# buttons_and_leds.net
KiCad netlist of a schematic drawn in Altium Designer
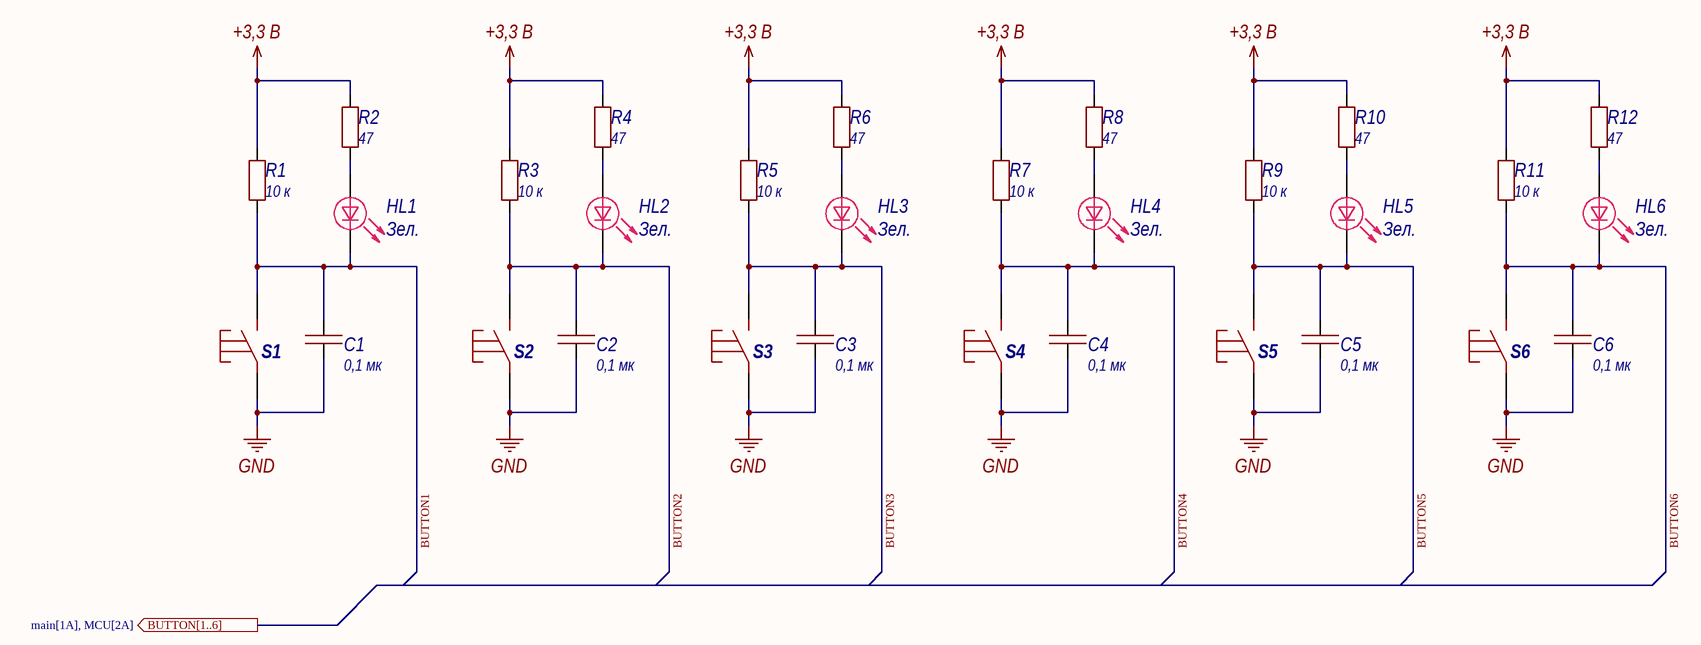
[diagram p0: buttons_and_leds.SchDoc]

(export (version "E")
  (design (tool "Eeschema 10.0.6"))
  (components
    (comp (ref "C1")
      (value "0,1 мк")
      (footprint "0603C")
      (description "Конденсатор 0603C ёмкостью 0,1 мк 10%, 50 В, X7R")
      (fields (field (name "PART NUMBER") "Capacitor_0,1u_10_50V_X7R_0603C") (field (name "TOLERANCE") "10%"))
      (libsource (lib "Hydrolib") (part "Capacitor"))
    )
    (comp (ref "C2")
      (value "0,1 мк")
      (footprint "0603C")
      (description "Конденсатор 0603C ёмкостью 0,1 мк 10%, 50 В, X7R")
      (fields (field (name "PART NUMBER") "Capacitor_0,1u_10_50V_X7R_0603C") (field (name "TOLERANCE") "10%"))
      (libsource (lib "Hydrolib") (part "Capacitor"))
    )
    (comp (ref "C3")
      (value "0,1 мк")
      (footprint "0603C")
      (description "Конденсатор 0603C ёмкостью 0,1 мк 10%, 50 В, X7R")
      (fields (field (name "PART NUMBER") "Capacitor_0,1u_10_50V_X7R_0603C") (field (name "TOLERANCE") "10%"))
      (libsource (lib "Hydrolib") (part "Capacitor"))
    )
    (comp (ref "C4")
      (value "0,1 мк")
      (footprint "0603C")
      (description "Конденсатор 0603C ёмкостью 0,1 мк 10%, 50 В, X7R")
      (fields (field (name "PART NUMBER") "Capacitor_0,1u_10_50V_X7R_0603C") (field (name "TOLERANCE") "10%"))
      (libsource (lib "Hydrolib") (part "Capacitor"))
    )
    (comp (ref "C5")
      (value "0,1 мк")
      (footprint "0603C")
      (description "Конденсатор 0603C ёмкостью 0,1 мк 10%, 50 В, X7R")
      (fields (field (name "PART NUMBER") "Capacitor_0,1u_10_50V_X7R_0603C") (field (name "TOLERANCE") "10%"))
      (libsource (lib "Hydrolib") (part "Capacitor"))
    )
    (comp (ref "C6")
      (value "0,1 мк")
      (footprint "0603C")
      (description "Конденсатор 0603C ёмкостью 0,1 мк 10%, 50 В, X7R")
      (fields (field (name "PART NUMBER") "Capacitor_0,1u_10_50V_X7R_0603C") (field (name "TOLERANCE") "10%"))
      (libsource (lib "Hydrolib") (part "Capacitor"))
    )
    (comp (ref "HL1")
      (value "LED")
      (footprint "0805D")
      (description "Светодиод")
      (fields (field (name "COLOR") "Зел."))
      (libsource (lib "Hydrolib") (part "LED"))
    )
    (comp (ref "HL2")
      (value "LED")
      (footprint "0805D")
      (description "Светодиод")
      (fields (field (name "COLOR") "Зел."))
      (libsource (lib "Hydrolib") (part "LED"))
    )
    (comp (ref "HL3")
      (value "LED")
      (footprint "0805D")
      (description "Светодиод")
      (fields (field (name "COLOR") "Зел."))
      (libsource (lib "Hydrolib") (part "LED"))
    )
    (comp (ref "HL4")
      (value "LED")
      (footprint "0805D")
      (description "Светодиод")
      (fields (field (name "COLOR") "Зел."))
      (libsource (lib "Hydrolib") (part "LED"))
    )
    (comp (ref "HL5")
      (value "LED")
      (footprint "0805D")
      (description "Светодиод")
      (fields (field (name "COLOR") "Зел."))
      (libsource (lib "Hydrolib") (part "LED"))
    )
    (comp (ref "HL6")
      (value "LED")
      (footprint "0805D")
      (description "Светодиод")
      (fields (field (name "COLOR") "Зел."))
      (libsource (lib "Hydrolib") (part "LED"))
    )
    (comp (ref "R1")
      (value "10 к")
      (footprint "0603R")
      (description "Резистор номиналом 10 кОм 1%")
      (fields (field (name "PART NUMBER") "Resistor_10k_1_0603") (field (name "TOLERANCE") "1%"))
      (libsource (lib "Hydrolib") (part "Resistor"))
    )
    (comp (ref "R2")
      (value "47")
      (footprint "0603R")
      (description "Резистор номиналом 47 Ом 1%")
      (fields (field (name "PART NUMBER") "Resistor_47_1_0603") (field (name "TOLERANCE") "1%"))
      (libsource (lib "Hydrolib") (part "Resistor"))
    )
    (comp (ref "R3")
      (value "10 к")
      (footprint "0603R")
      (description "Резистор номиналом 10 кОм 1%")
      (fields (field (name "PART NUMBER") "Resistor_10k_1_0603") (field (name "TOLERANCE") "1%"))
      (libsource (lib "Hydrolib") (part "Resistor"))
    )
    (comp (ref "R4")
      (value "47")
      (footprint "0603R")
      (description "Резистор номиналом 47 Ом 1%")
      (fields (field (name "PART NUMBER") "Resistor_47_1_0603") (field (name "TOLERANCE") "1%"))
      (libsource (lib "Hydrolib") (part "Resistor"))
    )
    (comp (ref "R5")
      (value "10 к")
      (footprint "0603R")
      (description "Резистор номиналом 10 кОм 1%")
      (fields (field (name "PART NUMBER") "Resistor_10k_1_0603") (field (name "TOLERANCE") "1%"))
      (libsource (lib "Hydrolib") (part "Resistor"))
    )
    (comp (ref "R6")
      (value "47")
      (footprint "0603R")
      (description "Резистор номиналом 47 Ом 1%")
      (fields (field (name "PART NUMBER") "Resistor_47_1_0603") (field (name "TOLERANCE") "1%"))
      (libsource (lib "Hydrolib") (part "Resistor"))
    )
    (comp (ref "R7")
      (value "10 к")
      (footprint "0603R")
      (description "Резистор номиналом 10 кОм 1%")
      (fields (field (name "PART NUMBER") "Resistor_10k_1_0603") (field (name "TOLERANCE") "1%"))
      (libsource (lib "Hydrolib") (part "Resistor"))
    )
    (comp (ref "R8")
      (value "47")
      (footprint "0603R")
      (description "Резистор номиналом 47 Ом 1%")
      (fields (field (name "PART NUMBER") "Resistor_47_1_0603") (field (name "TOLERANCE") "1%"))
      (libsource (lib "Hydrolib") (part "Resistor"))
    )
    (comp (ref "R9")
      (value "10 к")
      (footprint "0603R")
      (description "Резистор номиналом 10 кОм 1%")
      (fields (field (name "PART NUMBER") "Resistor_10k_1_0603") (field (name "TOLERANCE") "1%"))
      (libsource (lib "Hydrolib") (part "Resistor"))
    )
    (comp (ref "R10")
      (value "47")
      (footprint "0603R")
      (description "Резистор номиналом 47 Ом 1%")
      (fields (field (name "PART NUMBER") "Resistor_47_1_0603") (field (name "TOLERANCE") "1%"))
      (libsource (lib "Hydrolib") (part "Resistor"))
    )
    (comp (ref "R11")
      (value "10 к")
      (footprint "0603R")
      (description "Резистор номиналом 10 кОм 1%")
      (fields (field (name "PART NUMBER") "Resistor_10k_1_0603") (field (name "TOLERANCE") "1%"))
      (libsource (lib "Hydrolib") (part "Resistor"))
    )
    (comp (ref "R12")
      (value "47")
      (footprint "0603R")
      (description "Резистор номиналом 47 Ом 1%")
      (fields (field (name "PART NUMBER") "Resistor_47_1_0603") (field (name "TOLERANCE") "1%"))
      (libsource (lib "Hydrolib") (part "Resistor"))
    )
    (comp (ref "S1")
      (value "Button_DIP_12x12")
      (footprint "Button_DIP_12x12")
      (description "Тактовая кнопка, DIP 12 x 12 мм")
      (libsource (lib "Hydrolib") (part "Tact_button"))
    )
    (comp (ref "S2")
      (value "Button_DIP_12x12")
      (footprint "Button_DIP_12x12")
      (description "Тактовая кнопка, DIP 12 x 12 мм")
      (libsource (lib "Hydrolib") (part "Tact_button"))
    )
    (comp (ref "S3")
      (value "Button_DIP_12x12")
      (footprint "Button_DIP_12x12")
      (description "Тактовая кнопка, DIP 12 x 12 мм")
      (libsource (lib "Hydrolib") (part "Tact_button"))
    )
    (comp (ref "S4")
      (value "Button_DIP_12x12")
      (footprint "Button_DIP_12x12")
      (description "Тактовая кнопка, DIP 12 x 12 мм")
      (libsource (lib "Hydrolib") (part "Tact_button"))
    )
    (comp (ref "S5")
      (value "Button_DIP_12x12")
      (footprint "Button_DIP_12x12")
      (description "Тактовая кнопка, DIP 12 x 12 мм")
      (libsource (lib "Hydrolib") (part "Tact_button"))
    )
    (comp (ref "S6")
      (value "Button_DIP_12x12")
      (footprint "Button_DIP_12x12")
      (description "Тактовая кнопка, DIP 12 x 12 мм")
      (libsource (lib "Hydrolib") (part "Tact_button"))
    )
  )
  (nets
    (net (code "1") (name "+3,3 В") (class "Default")
      (node (ref "R1") (pin "2") (pinfunction "2_2") (pintype "passive"))
      (node (ref "R10") (pin "2") (pinfunction "2_2") (pintype "passive"))
      (node (ref "R11") (pin "2") (pinfunction "2_2") (pintype "passive"))
      (node (ref "R12") (pin "2") (pinfunction "2_2") (pintype "passive"))
      (node (ref "R2") (pin "2") (pinfunction "2_2") (pintype "passive"))
      (node (ref "R3") (pin "2") (pinfunction "2_2") (pintype "passive"))
      (node (ref "R4") (pin "2") (pinfunction "2_2") (pintype "passive"))
      (node (ref "R5") (pin "2") (pinfunction "2_2") (pintype "passive"))
      (node (ref "R6") (pin "2") (pinfunction "2_2") (pintype "passive"))
      (node (ref "R7") (pin "2") (pinfunction "2_2") (pintype "passive"))
      (node (ref "R8") (pin "2") (pinfunction "2_2") (pintype "passive"))
      (node (ref "R9") (pin "2") (pinfunction "2_2") (pintype "passive"))
    )
    (net (code "2") (name "/BUTTON1") (class "Default")
      (node (ref "C1") (pin "2") (pinfunction "2_2") (pintype "passive"))
      (node (ref "HL1") (pin "2") (pinfunction "2_2") (pintype "passive"))
      (node (ref "R1") (pin "1") (pinfunction "1_1") (pintype "passive"))
      (node (ref "S1") (pin "2") (pinfunction "2_2") (pintype "passive"))
    )
    (net (code "3") (name "/BUTTON2") (class "Default")
      (node (ref "C2") (pin "2") (pinfunction "2_2") (pintype "passive"))
      (node (ref "HL2") (pin "2") (pinfunction "2_2") (pintype "passive"))
      (node (ref "R3") (pin "1") (pinfunction "1_1") (pintype "passive"))
      (node (ref "S2") (pin "2") (pinfunction "2_2") (pintype "passive"))
    )
    (net (code "4") (name "/BUTTON3") (class "Default")
      (node (ref "C3") (pin "2") (pinfunction "2_2") (pintype "passive"))
      (node (ref "HL3") (pin "2") (pinfunction "2_2") (pintype "passive"))
      (node (ref "R5") (pin "1") (pinfunction "1_1") (pintype "passive"))
      (node (ref "S3") (pin "2") (pinfunction "2_2") (pintype "passive"))
    )
    (net (code "5") (name "/BUTTON4") (class "Default")
      (node (ref "C4") (pin "2") (pinfunction "2_2") (pintype "passive"))
      (node (ref "HL4") (pin "2") (pinfunction "2_2") (pintype "passive"))
      (node (ref "R7") (pin "1") (pinfunction "1_1") (pintype "passive"))
      (node (ref "S4") (pin "2") (pinfunction "2_2") (pintype "passive"))
    )
    (net (code "6") (name "/BUTTON5") (class "Default")
      (node (ref "C5") (pin "2") (pinfunction "2_2") (pintype "passive"))
      (node (ref "HL5") (pin "2") (pinfunction "2_2") (pintype "passive"))
      (node (ref "R9") (pin "1") (pinfunction "1_1") (pintype "passive"))
      (node (ref "S5") (pin "2") (pinfunction "2_2") (pintype "passive"))
    )
    (net (code "7") (name "/BUTTON6") (class "Default")
      (node (ref "C6") (pin "2") (pinfunction "2_2") (pintype "passive"))
      (node (ref "HL6") (pin "2") (pinfunction "2_2") (pintype "passive"))
      (node (ref "R11") (pin "1") (pinfunction "1_1") (pintype "passive"))
      (node (ref "S6") (pin "2") (pinfunction "2_2") (pintype "passive"))
    )
    (net (code "9") (name "GND") (class "Default")
      (node (ref "C1") (pin "1") (pinfunction "1_1") (pintype "passive"))
      (node (ref "C2") (pin "1") (pinfunction "1_1") (pintype "passive"))
      (node (ref "C3") (pin "1") (pinfunction "1_1") (pintype "passive"))
      (node (ref "C4") (pin "1") (pinfunction "1_1") (pintype "passive"))
      (node (ref "C5") (pin "1") (pinfunction "1_1") (pintype "passive"))
      (node (ref "C6") (pin "1") (pinfunction "1_1") (pintype "passive"))
      (node (ref "S1") (pin "1") (pinfunction "1_1") (pintype "passive"))
      (node (ref "S2") (pin "1") (pinfunction "1_1") (pintype "passive"))
      (node (ref "S3") (pin "1") (pinfunction "1_1") (pintype "passive"))
      (node (ref "S4") (pin "1") (pinfunction "1_1") (pintype "passive"))
      (node (ref "S5") (pin "1") (pinfunction "1_1") (pintype "passive"))
      (node (ref "S6") (pin "1") (pinfunction "1_1") (pintype "passive"))
    )
    (net (code "10") (name "Net-(HL1-Pad1)") (class "Default")
      (node (ref "HL1") (pin "1") (pinfunction "1_1") (pintype "passive"))
      (node (ref "R2") (pin "1") (pinfunction "1_1") (pintype "passive"))
    )
    (net (code "11") (name "Net-(HL2-Pad1)") (class "Default")
      (node (ref "HL2") (pin "1") (pinfunction "1_1") (pintype "passive"))
      (node (ref "R4") (pin "1") (pinfunction "1_1") (pintype "passive"))
    )
    (net (code "12") (name "Net-(HL3-Pad1)") (class "Default")
      (node (ref "HL3") (pin "1") (pinfunction "1_1") (pintype "passive"))
      (node (ref "R6") (pin "1") (pinfunction "1_1") (pintype "passive"))
    )
    (net (code "13") (name "Net-(HL4-Pad1)") (class "Default")
      (node (ref "HL4") (pin "1") (pinfunction "1_1") (pintype "passive"))
      (node (ref "R8") (pin "1") (pinfunction "1_1") (pintype "passive"))
    )
    (net (code "14") (name "Net-(HL5-Pad1)") (class "Default")
      (node (ref "HL5") (pin "1") (pinfunction "1_1") (pintype "passive"))
      (node (ref "R10") (pin "1") (pinfunction "1_1") (pintype "passive"))
    )
    (net (code "15") (name "Net-(HL6-Pad1)") (class "Default")
      (node (ref "HL6") (pin "1") (pinfunction "1_1") (pintype "passive"))
      (node (ref "R12") (pin "1") (pinfunction "1_1") (pintype "passive"))
    )
  )
)
